# hvac-notification-extension-v1.net
KiCad netlist of a schematic drawn in EAGLE
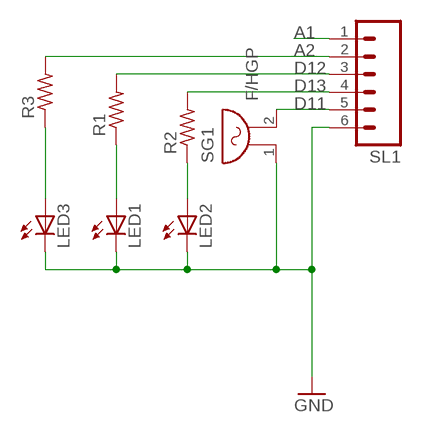
[diagram p0: schematic, sheet 1]

(export (version "E")
  (design (tool "Eeschema 10.0.6"))
  (components
    (comp (ref "LED1")
      (value "LED3MM")
      (footprint "eagle-import:LED3MM")
      (libsource (lib "eagle-import") (part "LED3MM"))
    )
    (comp (ref "LED2")
      (value "LED3MM")
      (footprint "eagle-import:LED3MM")
      (libsource (lib "eagle-import") (part "LED3MM"))
    )
    (comp (ref "LED3")
      (value "LED3MM")
      (footprint "eagle-import:LED3MM")
      (libsource (lib "eagle-import") (part "LED3MM"))
    )
    (comp (ref "R1")
      (value "R-US_R0603")
      (footprint "eagle-import:R0603")
      (libsource (lib "eagle-import") (part "R-US_R0603"))
    )
    (comp (ref "R2")
      (value "R-US_R0603")
      (footprint "eagle-import:R0603")
      (libsource (lib "eagle-import") (part "R-US_R0603"))
    )
    (comp (ref "R3")
      (value "R-US_R0603")
      (footprint "eagle-import:R0603")
      (libsource (lib "eagle-import") (part "R-US_R0603"))
    )
    (comp (ref "SG1")
      (value "F/HGP")
      (footprint "eagle-import:F_HGP")
      (libsource (lib "eagle-import") (part "F/HGP"))
    )
    (comp (ref "SL1")
      (value "M06")
      (footprint "eagle-import:06P")
      (libsource (lib "eagle-import") (part "M06"))
    )
  )
  (nets
    (net (code "1") (name "/A1") (class "Default")
      (node (ref "SL1") (pin "1") (pinfunction "1_1") (pintype "passive"))
    )
    (net (code "2") (name "/A2") (class "Default")
      (node (ref "R3") (pin "2") (pinfunction "2_2") (pintype "passive"))
      (node (ref "SL1") (pin "2") (pinfunction "2_2") (pintype "passive"))
    )
    (net (code "3") (name "/D11") (class "Default")
      (node (ref "SG1") (pin "2") (pinfunction "2_2") (pintype "passive"))
      (node (ref "SL1") (pin "5") (pinfunction "5_5") (pintype "passive"))
    )
    (net (code "4") (name "/D12") (class "Default")
      (node (ref "R1") (pin "2") (pinfunction "2_2") (pintype "passive"))
      (node (ref "SL1") (pin "3") (pinfunction "3_3") (pintype "passive"))
    )
    (net (code "5") (name "/D13") (class "Default")
      (node (ref "R2") (pin "2") (pinfunction "2_2") (pintype "passive"))
      (node (ref "SL1") (pin "4") (pinfunction "4_4") (pintype "passive"))
    )
    (net (code "6") (name "GND") (class "Default")
      (node (ref "LED1") (pin "K") (pinfunction "C_K") (pintype "passive"))
      (node (ref "LED2") (pin "K") (pinfunction "C_K") (pintype "passive"))
      (node (ref "LED3") (pin "K") (pinfunction "C_K") (pintype "passive"))
      (node (ref "SG1") (pin "1") (pinfunction "1_1") (pintype "passive"))
      (node (ref "SL1") (pin "6") (pinfunction "6_6") (pintype "passive"))
    )
    (net (code "7") (name "Net-(LED1-PadA)") (class "Default")
      (node (ref "LED1") (pin "A") (pinfunction "A_A") (pintype "passive"))
      (node (ref "R1") (pin "1") (pinfunction "1_1") (pintype "passive"))
    )
    (net (code "8") (name "Net-(LED2-PadA)") (class "Default")
      (node (ref "LED2") (pin "A") (pinfunction "A_A") (pintype "passive"))
      (node (ref "R2") (pin "1") (pinfunction "1_1") (pintype "passive"))
    )
    (net (code "9") (name "Net-(LED3-PadA)") (class "Default")
      (node (ref "LED3") (pin "A") (pinfunction "A_A") (pintype "passive"))
      (node (ref "R3") (pin "1") (pinfunction "1_1") (pintype "passive"))
    )
  )
)
